# analogPath.net
KiCad netlist of a schematic drawn in Altium Designer
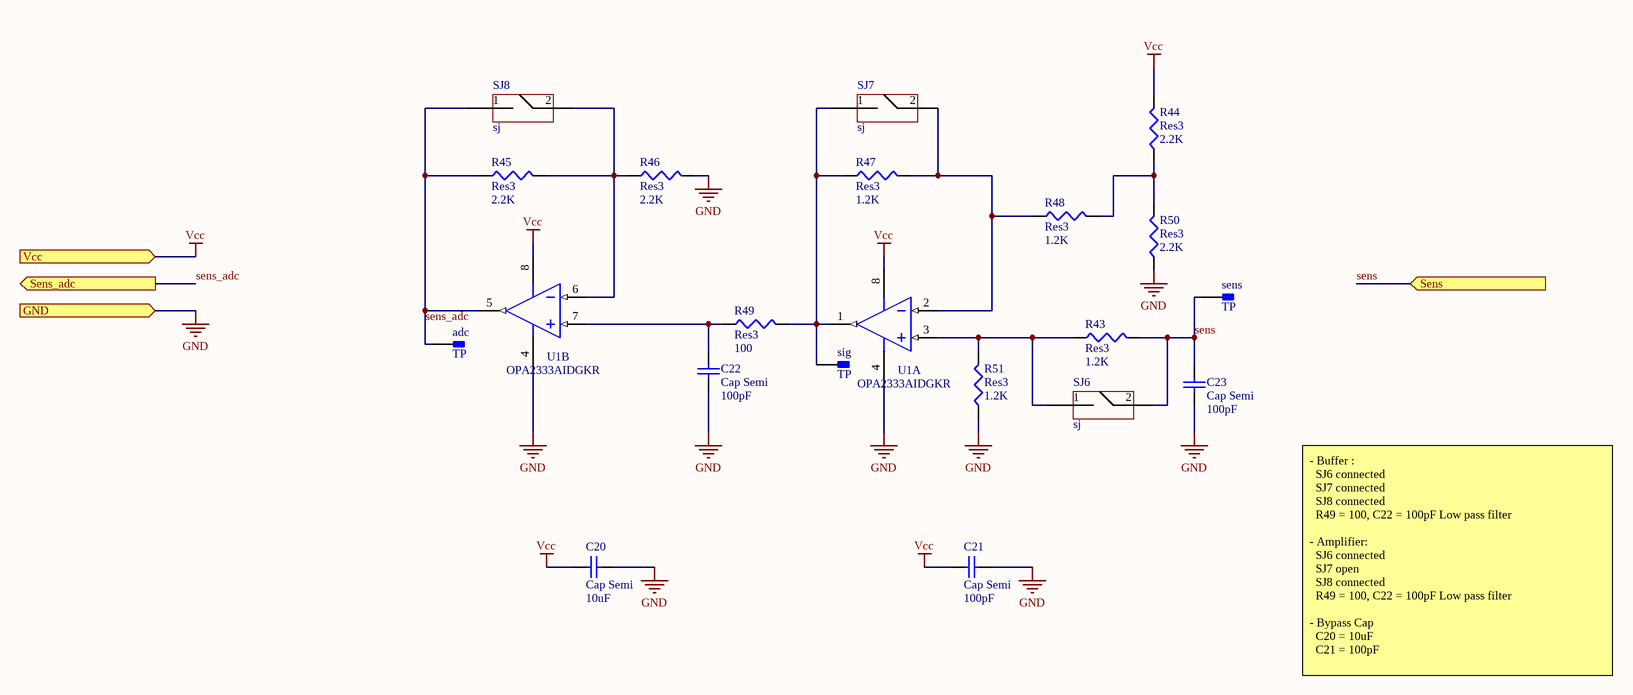
[diagram p0: analogPath.SchDoc]

(export (version "E")
  (design (tool "Eeschema 10.0.6"))
  (components
    (comp (ref "adc")
      (value "TP")
      (footprint "TP")
      (description "Solder test point")
      (libsource (lib "IoWLabs") (part "TP"))
    )
    (comp (ref "C20")
      (value "Cap Semi")
      (footprint "1608[0603]")
      (description "Capacitor (Semiconductor SIM Model)")
      (fields
        (field (name "ALTIUM_VALUE") "10uF")
        (field (name "MANUFACTURER") "Samsung Electro-Mechanics")
        (field (name "MANUFACTURER PART NUMBER") "CL10A106MQ8NNNC")
        (field (name "PUBLISHER") "Altium Limited")
      )
      (libsource (lib "Miscellaneous Devices") (part "Cap Semi"))
    )
    (comp (ref "C21")
      (value "Cap Semi")
      (footprint "1608[0603]")
      (description "Capacitor (Semiconductor SIM Model)")
      (fields
        (field (name "ALTIUM_VALUE") "100pF")
        (field (name "MANUFACTURER") "YAGEO")
        (field (name "MANUFACTURER PART NUMBER") "CC0603KRX7R8BB101")
        (field (name "PUBLISHER") "Altium Limited")
      )
      (libsource (lib "Miscellaneous Devices") (part "Cap Semi"))
    )
    (comp (ref "C22")
      (value "Cap Semi")
      (footprint "1608[0603]")
      (description "Capacitor (Semiconductor SIM Model)")
      (fields
        (field (name "ALTIUM_VALUE") "100pF")
        (field (name "MANUFACTURER") "YAGEO")
        (field (name "MANUFACTURER PART NUMBER") "CC0603KRX7R8BB101")
        (field (name "PUBLISHER") "Altium Limited")
      )
      (libsource (lib "Miscellaneous Devices") (part "Cap Semi"))
    )
    (comp (ref "C23")
      (value "Cap Semi")
      (footprint "1608[0603]")
      (description "Capacitor (Semiconductor SIM Model)")
      (fields
        (field (name "ALTIUM_VALUE") "100pF")
        (field (name "MANUFACTURER") "YAGEO")
        (field (name "MANUFACTURER PART NUMBER") "CC0603KRX7R8BB101")
        (field (name "PUBLISHER") "Altium Limited")
      )
      (libsource (lib "Miscellaneous Devices") (part "Cap Semi"))
    )
    (comp (ref "R43")
      (value "Res3")
      (footprint "J1-0603")
      (description "Resistor")
      (fields
        (field (name "ALTIUM_VALUE") "1.2K")
        (field (name "MANUFACTURER PART NUMBER") "MCR03EZPFX1201")
        (field (name "MANUFACTURER") "ROHM Semicon")
        (field (name "PUBLISHER") "Altium Limited")
      )
      (libsource (lib "Miscellaneous Devices") (part "Res3"))
    )
    (comp (ref "R44")
      (value "Res3")
      (footprint "J1-0603")
      (description "Resistor")
      (fields
        (field (name "ALTIUM_VALUE") "2.2K")
        (field (name "MANUFACTURER PART NUMBER") "RC0603FR-072K2L")
        (field (name "MANUFACTURER") "YAGEO")
        (field (name "PUBLISHER") "Altium Limited")
      )
      (libsource (lib "Miscellaneous Devices") (part "Res3"))
    )
    (comp (ref "R45")
      (value "Res3")
      (footprint "J1-0603")
      (description "Resistor")
      (fields
        (field (name "ALTIUM_VALUE") "2.2K")
        (field (name "MANUFACTURER PART NUMBER") "RC0603FR-072K2L")
        (field (name "MANUFACTURER") "YAGEO")
        (field (name "PUBLISHER") "Altium Limited")
      )
      (libsource (lib "Miscellaneous Devices") (part "Res3"))
    )
    (comp (ref "R46")
      (value "Res3")
      (footprint "J1-0603")
      (description "Resistor")
      (fields
        (field (name "ALTIUM_VALUE") "2.2K")
        (field (name "MANUFACTURER PART NUMBER") "RC0603FR-072K2L")
        (field (name "MANUFACTURER") "YAGEO")
        (field (name "PUBLISHER") "Altium Limited")
      )
      (libsource (lib "Miscellaneous Devices") (part "Res3"))
    )
    (comp (ref "R47")
      (value "Res3")
      (footprint "J1-0603")
      (description "Resistor")
      (fields
        (field (name "ALTIUM_VALUE") "1.2K")
        (field (name "MANUFACTURER PART NUMBER") "MCR03EZPFX1201")
        (field (name "MANUFACTURER") "ROHM Semicon")
        (field (name "PUBLISHER") "Altium Limited")
      )
      (libsource (lib "Miscellaneous Devices") (part "Res3"))
    )
    (comp (ref "R48")
      (value "Res3")
      (footprint "J1-0603")
      (description "Resistor")
      (fields
        (field (name "ALTIUM_VALUE") "1.2K")
        (field (name "MANUFACTURER PART NUMBER") "MCR03EZPFX1201")
        (field (name "MANUFACTURER") "ROHM Semicon")
        (field (name "PUBLISHER") "Altium Limited")
      )
      (libsource (lib "Miscellaneous Devices") (part "Res3"))
    )
    (comp (ref "R49")
      (value "Res3")
      (footprint "J1-0603")
      (description "Resistor")
      (fields
        (field (name "ALTIUM_VALUE") "100")
        (field (name "MANUFACTURER PART NUMBER") "RC0603FR-07100RL")
        (field (name "MANUFACTURER") "YAGEO")
        (field (name "PUBLISHER") "Altium Limited")
      )
      (libsource (lib "Miscellaneous Devices") (part "Res3"))
    )
    (comp (ref "R50")
      (value "Res3")
      (footprint "J1-0603")
      (description "Resistor")
      (fields
        (field (name "ALTIUM_VALUE") "2.2K")
        (field (name "MANUFACTURER PART NUMBER") "RC0603FR-072K2L")
        (field (name "MANUFACTURER") "YAGEO")
        (field (name "PUBLISHER") "Altium Limited")
      )
      (libsource (lib "Miscellaneous Devices") (part "Res3"))
    )
    (comp (ref "R51")
      (value "Res3")
      (footprint "J1-0603")
      (description "Resistor")
      (fields
        (field (name "ALTIUM_VALUE") "1.2K")
        (field (name "MANUFACTURER PART NUMBER") "MCR03EZPFX1201")
        (field (name "MANUFACTURER") "ROHM Semicon")
        (field (name "PUBLISHER") "Altium Limited")
      )
      (libsource (lib "Miscellaneous Devices") (part "Res3"))
    )
    (comp (ref "sens")
      (value "TP")
      (footprint "TP")
      (description "Solder test point")
      (libsource (lib "IoWLabs") (part "TP"))
    )
    (comp (ref "sig")
      (value "TP")
      (footprint "TP")
      (description "Solder test point")
      (libsource (lib "IoWLabs") (part "TP"))
    )
    (comp (ref "SJ6")
      (value "sj")
      (footprint "SJ2")
      (description "solder jumper generic")
      (libsource (lib "IoWLabs") (part "Jumper"))
    )
    (comp (ref "SJ7")
      (value "sj")
      (footprint "SJ2")
      (description "solder jumper generic")
      (libsource (lib "IoWLabs") (part "Jumper"))
    )
    (comp (ref "SJ8")
      (value "sj")
      (footprint "SJ2")
      (description "solder jumper generic")
      (libsource (lib "IoWLabs") (part "Jumper"))
    )
    (comp (ref "U1")
      (value "OPA2333AIDGKR")
      (footprint "MSOP-8")
      (description "Precision OpAmps Zero-Drift 2 1.8V ~ 5.5V, ±0.9V ~ 2.75V 350kHz 0.16 V/us MSOP-8 RoHS")
      (fields (field (name "MANUFACTURER") "Texas Instruments"))
      (libsource (lib "IoWLabs") (part "OPA2333"))
    )
  )
  (nets
    (net (code "1") (name "/sens") (class "Default")
      (node (ref "C23") (pin "2") (pinfunction "2_2") (pintype "passive"))
      (node (ref "R43") (pin "2") (pinfunction "2_2") (pintype "passive"))
      (node (ref "SJ6") (pin "2") (pinfunction "2_2") (pintype "passive"))
      (node (ref "sens") (pin "1") (pinfunction "1_1") (pintype "passive"))
    )
    (net (code "2") (name "/sens_adc") (class "Default")
      (node (ref "R45") (pin "1") (pinfunction "1_1") (pintype "passive"))
      (node (ref "SJ8") (pin "1") (pinfunction "1_1") (pintype "passive"))
      (node (ref "U1") (pin "5") (pinfunction "OUT_A_5") (pintype "output"))
      (node (ref "adc") (pin "1") (pinfunction "1_1") (pintype "passive"))
    )
    (net (code "3") (name "GND") (class "Default")
      (node (ref "C20") (pin "1") (pinfunction "1_1") (pintype "passive"))
      (node (ref "C21") (pin "2") (pinfunction "2_2") (pintype "passive"))
      (node (ref "C22") (pin "1") (pinfunction "1_1") (pintype "passive"))
      (node (ref "C23") (pin "1") (pinfunction "1_1") (pintype "passive"))
      (node (ref "R46") (pin "2") (pinfunction "2_2") (pintype "passive"))
      (node (ref "R50") (pin "1") (pinfunction "1_1") (pintype "passive"))
      (node (ref "R51") (pin "1") (pinfunction "1_1") (pintype "passive"))
      (node (ref "U1") (pin "4") (pinfunction "-V_4") (pintype "passive"))
    )
    (net (code "4") (name "Net-(R44-Pad1)") (class "Default")
      (node (ref "R44") (pin "1") (pinfunction "1_1") (pintype "passive"))
      (node (ref "R48") (pin "2") (pinfunction "2_2") (pintype "passive"))
      (node (ref "R50") (pin "2") (pinfunction "2_2") (pintype "passive"))
    )
    (net (code "5") (name "Net-(U1A-+IN_A)") (class "Default")
      (node (ref "R43") (pin "1") (pinfunction "1_1") (pintype "passive"))
      (node (ref "R51") (pin "2") (pinfunction "2_2") (pintype "passive"))
      (node (ref "SJ6") (pin "1") (pinfunction "1_1") (pintype "passive"))
      (node (ref "U1") (pin "3") (pinfunction "+IN_A_3") (pintype "input"))
    )
    (net (code "6") (name "Net-(U1A--IN_A)") (class "Default")
      (node (ref "R47") (pin "2") (pinfunction "2_2") (pintype "passive"))
      (node (ref "R48") (pin "1") (pinfunction "1_1") (pintype "passive"))
      (node (ref "SJ7") (pin "2") (pinfunction "2_2") (pintype "passive"))
      (node (ref "U1") (pin "2") (pinfunction "-IN_A_2") (pintype "input"))
    )
    (net (code "7") (name "Net-(U1A-OUT_A)") (class "Default")
      (node (ref "R47") (pin "1") (pinfunction "1_1") (pintype "passive"))
      (node (ref "R49") (pin "2") (pinfunction "2_2") (pintype "passive"))
      (node (ref "SJ7") (pin "1") (pinfunction "1_1") (pintype "passive"))
      (node (ref "U1") (pin "1") (pinfunction "OUT_A_1") (pintype "output"))
      (node (ref "sig") (pin "1") (pinfunction "1_1") (pintype "passive"))
    )
    (net (code "8") (name "Net-(U1B-+IN_A)") (class "Default")
      (node (ref "C22") (pin "2") (pinfunction "2_2") (pintype "passive"))
      (node (ref "R49") (pin "1") (pinfunction "1_1") (pintype "passive"))
      (node (ref "U1") (pin "7") (pinfunction "+IN_A_7") (pintype "input"))
    )
    (net (code "9") (name "Net-(U1B--IN_A)") (class "Default")
      (node (ref "R45") (pin "2") (pinfunction "2_2") (pintype "passive"))
      (node (ref "R46") (pin "1") (pinfunction "1_1") (pintype "passive"))
      (node (ref "SJ8") (pin "2") (pinfunction "2_2") (pintype "passive"))
      (node (ref "U1") (pin "6") (pinfunction "-IN_A_6") (pintype "input"))
    )
    (net (code "10") (name "Vcc") (class "Default")
      (node (ref "C20") (pin "2") (pinfunction "2_2") (pintype "passive"))
      (node (ref "C21") (pin "1") (pinfunction "1_1") (pintype "passive"))
      (node (ref "R44") (pin "2") (pinfunction "2_2") (pintype "passive"))
      (node (ref "U1") (pin "8") (pinfunction "+V_8") (pintype "passive"))
    )
  )
)
